# power_DCDC_steup_33.net
KiCad netlist of a schematic drawn in Altium Designer
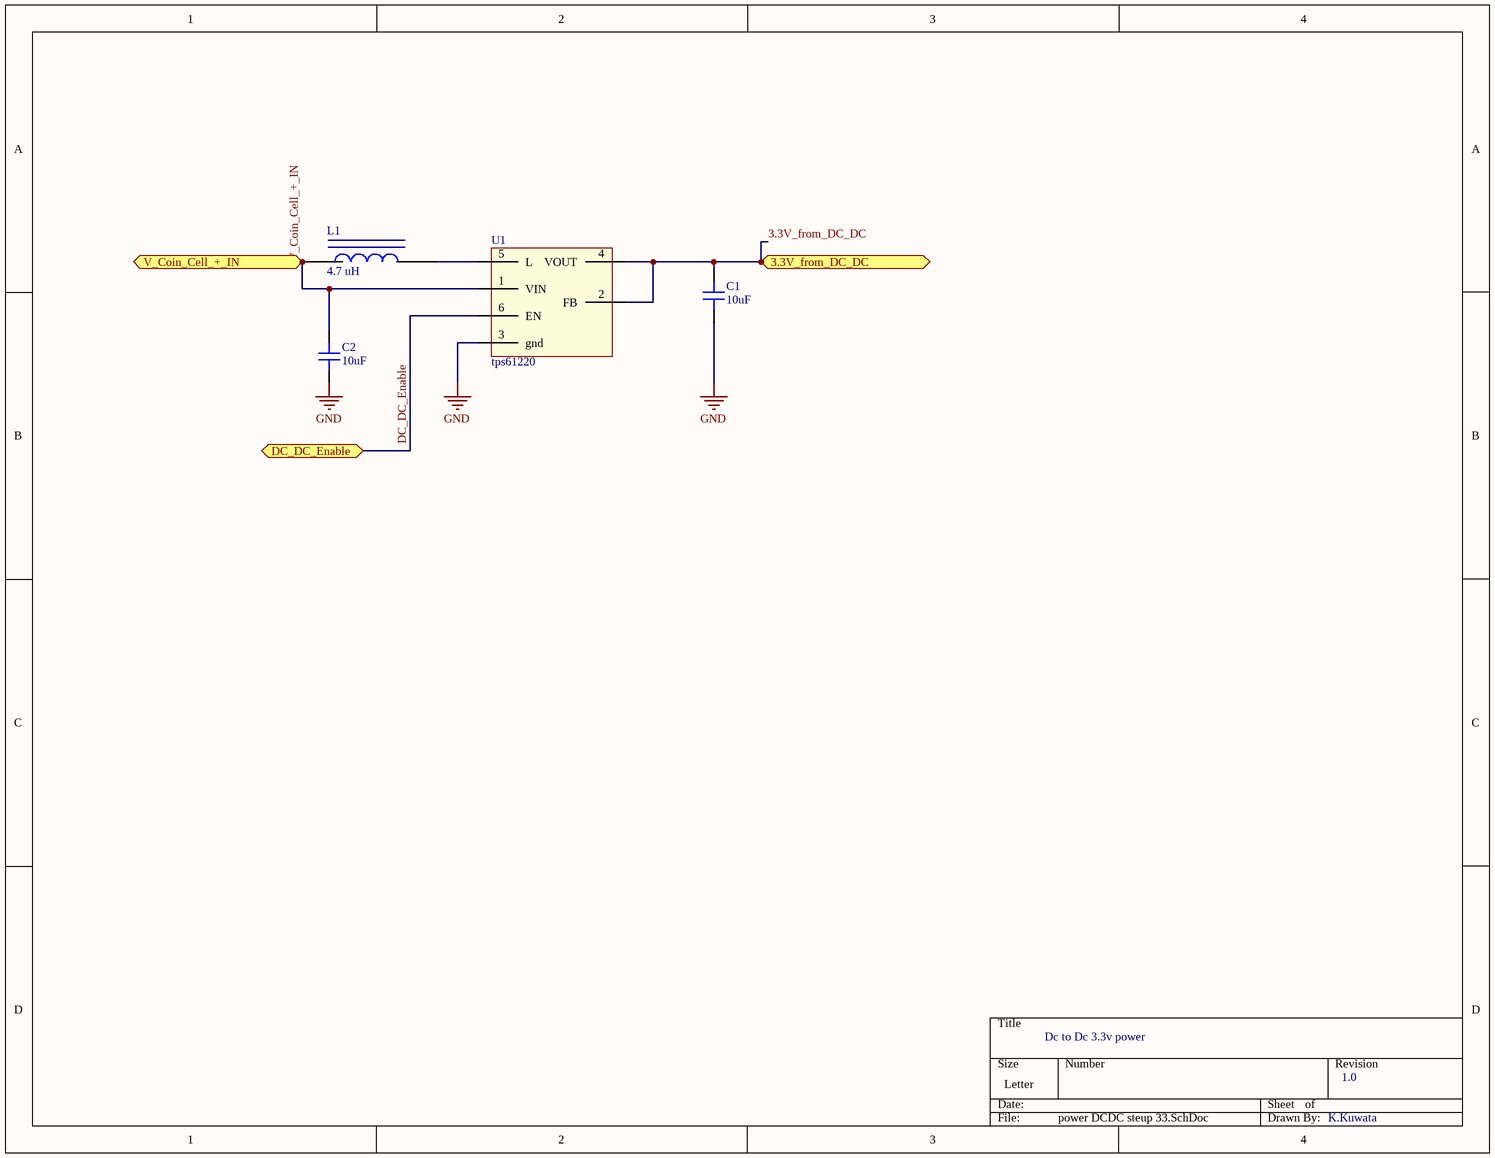
[diagram p0: power DCDC steup 33.SchDoc]

(export (version "E")
  (design (tool "Eeschema 10.0.6"))
  (components
    (comp (ref "C1")
      (value "10uF")
      (footprint "CAP 0402/1005")
      (description "CAP CER 0.1UF 16V X7R 0402")
      (fields
        (field (name "PART NUMBER") "C1005X7R1C104K050BC")
        (field (name "MANUFACTURER") "TDK Corporation")
      )
      (libsource (lib "Celestial Library Database") (part "Capacitor"))
    )
    (comp (ref "C2")
      (value "10uF")
      (footprint "CAP 0402/1005")
      (description "CAP CER 0.1UF 16V X7R 0402")
      (fields
        (field (name "PART NUMBER") "C1005X7R1C104K050BC")
        (field (name "MANUFACTURER") "TDK Corporation")
      )
      (libsource (lib "Celestial Library Database") (part "Capacitor"))
    )
    (comp (ref "L1")
      (value "4.7 uH")
      (footprint "4.7 uH 1008 case")
      (libsource (lib "KevinKuwata_Library") (part "inductor"))
    )
    (comp (ref "U1")
      (value "tps61220")
      (footprint "SOT65P210X110-6N")
      (libsource (lib "KevinKuwata_Library") (part "tps61220"))
    )
  )
  (nets
    (net (code "1") (name "/3.3V_from_DC_DC") (class "Default")
      (node (ref "C1") (pin "2") (pinfunction "2_2") (pintype "passive"))
      (node (ref "U1") (pin "2") (pinfunction "FB_2") (pintype "passive"))
      (node (ref "U1") (pin "4") (pinfunction "VOUT_4") (pintype "passive"))
    )
    (net (code "2") (name "/DC_DC_Enable") (class "Default")
      (node (ref "U1") (pin "6") (pinfunction "EN_6") (pintype "passive"))
    )
    (net (code "3") (name "/V_Coin_Cell_+_IN") (class "Default")
      (node (ref "C2") (pin "2") (pinfunction "2_2") (pintype "passive"))
      (node (ref "L1") (pin "1") (pinfunction "1_1") (pintype "passive"))
      (node (ref "U1") (pin "1") (pinfunction "VIN_1") (pintype "passive"))
    )
    (net (code "4") (name "GND") (class "Default")
      (node (ref "C1") (pin "1") (pinfunction "1_1") (pintype "passive"))
      (node (ref "C2") (pin "1") (pinfunction "1_1") (pintype "passive"))
      (node (ref "U1") (pin "3") (pinfunction "gnd_3") (pintype "passive"))
    )
    (net (code "5") (name "Net-(U1-L)") (class "Default")
      (node (ref "L1") (pin "2") (pinfunction "2_2") (pintype "passive"))
      (node (ref "U1") (pin "5") (pinfunction "L_5") (pintype "passive"))
    )
  )
)
